# BIRDS-5_1U__X-panel_EM_PUPV_v3_2.net
KiCad netlist of a schematic drawn in EAGLE
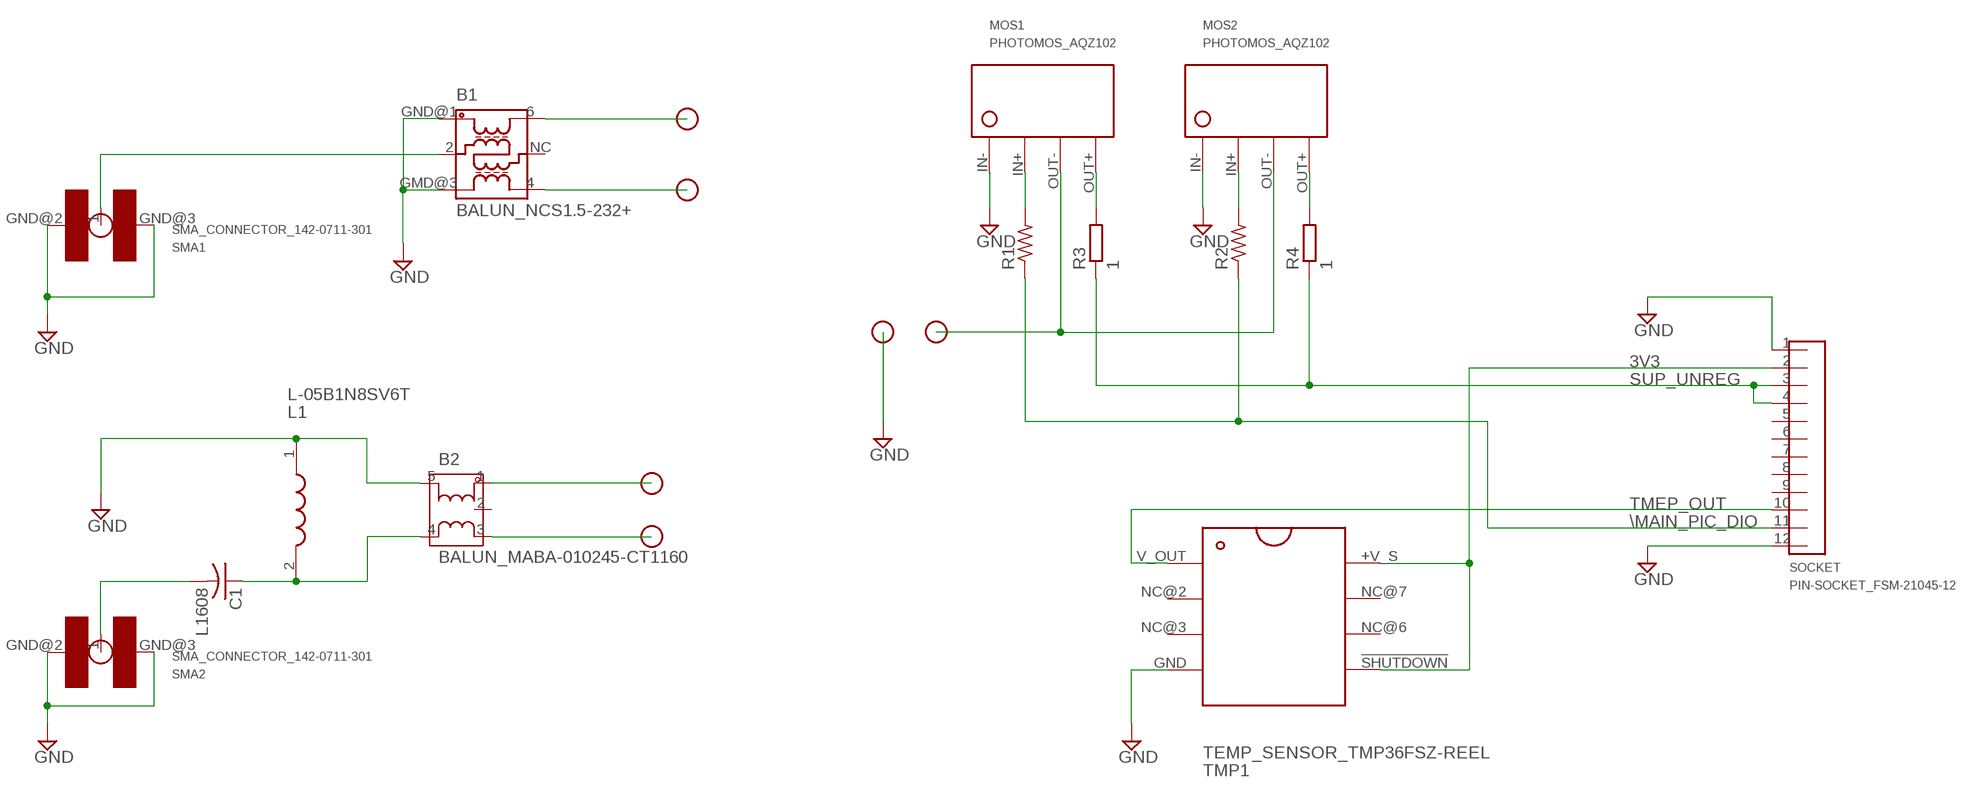
[diagram p0: schematic, sheet 1]

(export (version "E")
  (design (tool "Eeschema 10.0.6"))
  (components
    (comp (ref "B1")
      (value "BALUN_NCS1.5-232+")
      (footprint "eagle-import:NCS1.5-232+")
      (libsource (lib "eagle-import") (part "BALUN_NCS1.5-232+"))
    )
    (comp (ref "B2")
      (value "BALUN_MABA-010245-CT1160")
      (footprint "eagle-import:MABA-010245-CT1160")
      (libsource (lib "eagle-import") (part "BALUN_MABA-010245-CT1160"))
    )
    (comp (ref "C1")
      (value "L1608")
      (footprint "eagle-import:L1608")
      (libsource (lib "eagle-import") (part "L1608"))
    )
    (comp (ref "FD1")
      (value "FEED_POINT_HEAT_KNIFE")
      (footprint "eagle-import:FEED_POINT_HEAT_KNIFE")
      (libsource (lib "eagle-import") (part "FEED_POINT_HEAT_KNIFE"))
    )
    (comp (ref "FD2")
      (value "FEED_POINT_HEAT_KNIFE")
      (footprint "eagle-import:FEED_POINT_HEAT_KNIFE")
      (libsource (lib "eagle-import") (part "FEED_POINT_HEAT_KNIFE"))
    )
    (comp (ref "FP1_UHF")
      (value "FEED_POINT")
      (footprint "eagle-import:FEED_POINT")
      (libsource (lib "eagle-import") (part "FEED_POINT"))
    )
    (comp (ref "FP2_UHF")
      (value "FEED_POINT")
      (footprint "eagle-import:FEED_POINT")
      (libsource (lib "eagle-import") (part "FEED_POINT"))
    )
    (comp (ref "FP3")
      (value "FEED_POINT")
      (footprint "eagle-import:FEED_POINT")
      (libsource (lib "eagle-import") (part "FEED_POINT"))
    )
    (comp (ref "FP4")
      (value "FEED_POINT")
      (footprint "eagle-import:FEED_POINT")
      (libsource (lib "eagle-import") (part "FEED_POINT"))
    )
    (comp (ref "L1")
      (value "L-05B1N8SV6T")
      (footprint "eagle-import:INDC0603X33N")
      (libsource (lib "eagle-import") (part "L-05B1N8SV6T"))
    )
    (comp (ref "MOS1")
      (value "PHOTOMOS_AQZ102")
      (footprint "eagle-import:AQZ102")
      (libsource (lib "eagle-import") (part "PHOTOMOS_AQZ102"))
    )
    (comp (ref "MOS2")
      (value "PHOTOMOS_AQZ102")
      (footprint "eagle-import:AQZ102")
      (libsource (lib "eagle-import") (part "PHOTOMOS_AQZ102"))
    )
    (comp (ref "R1")
      (value "R-US_R0402")
      (footprint "eagle-import:R0402")
      (libsource (lib "eagle-import") (part "R-US_R0402"))
    )
    (comp (ref "R2")
      (value "R-US_R0402")
      (footprint "eagle-import:R0402")
      (libsource (lib "eagle-import") (part "R-US_R0402"))
    )
    (comp (ref "R3")
      (value "1")
      (footprint "eagle-import:R1218")
      (libsource (lib "eagle-import") (part "R-EU_R1218"))
    )
    (comp (ref "R4")
      (value "1")
      (footprint "eagle-import:R1218")
      (libsource (lib "eagle-import") (part "R-EU_R1218"))
    )
    (comp (ref "SMA1")
      (value "SMA_CONNECTOR_142-0711-301")
      (footprint "eagle-import:142-0711-301")
      (libsource (lib "eagle-import") (part "SMA_CONNECTOR_142-0711-301"))
    )
    (comp (ref "SMA2")
      (value "SMA_CONNECTOR_142-0711-301")
      (footprint "eagle-import:142-0711-301")
      (libsource (lib "eagle-import") (part "SMA_CONNECTOR_142-0711-301"))
    )
    (comp (ref "SOCKET")
      (value "PIN-SOCKET_FSM-21045-12")
      (footprint "eagle-import:PIN-SOCKET_FSM-21045-12")
      (libsource (lib "eagle-import") (part "PIN-SOCKET_FSM-21045-12"))
    )
    (comp (ref "TMP1")
      (value "TEMP_SENSOR_TMP36FSZ-REEL")
      (footprint "eagle-import:TMP36FSZ-REEL")
      (libsource (lib "eagle-import") (part "TEMP_SENSOR_TMP36FSZ-REEL"))
    )
  )
  (nets
    (net (code "1") (name "/3V3") (class "Default")
      (node (ref "SOCKET") (pin "2") (pinfunction "P$2_2") (pintype "bidirectional"))
      (node (ref "TMP1") (pin "!SHUTDOWN!") (pinfunction "~{SHUTDOWN}_!SHUTDOWN!") (pintype "input"))
      (node (ref "TMP1") (pin "+V_S") (pinfunction "+V_S_+V_S") (pintype "power_in"))
    )
    (net (code "2") (name "/SUP_UNREG") (class "Default")
      (node (ref "R3") (pin "1") (pinfunction "1_1") (pintype "passive"))
      (node (ref "R4") (pin "1") (pinfunction "1_1") (pintype "passive"))
      (node (ref "SOCKET") (pin "3") (pinfunction "P$3_3") (pintype "bidirectional"))
      (node (ref "SOCKET") (pin "4") (pinfunction "P$4_4") (pintype "bidirectional"))
    )
    (net (code "3") (name "/TMEP_OUT") (class "Default")
      (node (ref "SOCKET") (pin "10") (pinfunction "P$10_10") (pintype "bidirectional"))
      (node (ref "TMP1") (pin "V_OUT") (pinfunction "V_OUT_V_OUT") (pintype "output"))
    )
    (net (code "4") (name "/\\MAIN_PIC_DIO") (class "Default")
      (node (ref "R1") (pin "1") (pinfunction "1_1") (pintype "passive"))
      (node (ref "R2") (pin "1") (pinfunction "1_1") (pintype "passive"))
      (node (ref "SOCKET") (pin "11") (pinfunction "P$11_11") (pintype "bidirectional"))
    )
    (net (code "5") (name "GND") (class "Default")
      (node (ref "B1") (pin "GMD@3") (pinfunction "GND_GMD@3") (pintype "passive"))
      (node (ref "B1") (pin "GND@1") (pinfunction "GND_GND@1") (pintype "passive"))
      (node (ref "B2") (pin "5") (pinfunction "5_5") (pintype "passive"))
      (node (ref "FD2") (pin "FP") (pinfunction "FEED_POINT_FP") (pintype "passive"))
      (node (ref "L1") (pin "1") (pinfunction "1_1") (pintype "bidirectional"))
      (node (ref "MOS1") (pin "IN-") (pinfunction "IN-_IN-") (pintype "bidirectional"))
      (node (ref "MOS2") (pin "IN-") (pinfunction "IN-_IN-") (pintype "bidirectional"))
      (node (ref "SMA1") (pin "GND@2") (pinfunction "GND_GND@2") (pintype "passive"))
      (node (ref "SMA1") (pin "GND@3") (pinfunction "GMD_GND@3") (pintype "passive"))
      (node (ref "SMA2") (pin "GND@2") (pinfunction "GND_GND@2") (pintype "passive"))
      (node (ref "SMA2") (pin "GND@3") (pinfunction "GMD_GND@3") (pintype "passive"))
      (node (ref "SOCKET") (pin "1") (pinfunction "P$1_1") (pintype "bidirectional"))
      (node (ref "SOCKET") (pin "12") (pinfunction "P$12_12") (pintype "bidirectional"))
      (node (ref "TMP1") (pin "GND") (pinfunction "GND_GND") (pintype "power_in"))
    )
    (net (code "6") (name "Net-(B1-Pad2)") (class "Default")
      (node (ref "B1") (pin "2") (pinfunction "2_2") (pintype "passive"))
      (node (ref "SMA1") (pin "1") (pinfunction "1_1") (pintype "passive"))
    )
    (net (code "7") (name "Net-(B2-Pad4)") (class "Default")
      (node (ref "B2") (pin "4") (pinfunction "4_4") (pintype "passive"))
      (node (ref "C1") (pin "1") (pinfunction "1_1") (pintype "passive"))
      (node (ref "L1") (pin "2") (pinfunction "2_2") (pintype "bidirectional"))
    )
    (net (code "8") (name "Net-(C1-Pad2)") (class "Default")
      (node (ref "C1") (pin "2") (pinfunction "2_2") (pintype "passive"))
      (node (ref "SMA2") (pin "1") (pinfunction "1_1") (pintype "passive"))
    )
    (net (code "9") (name "Net-(FD1-FEED_POINT)") (class "Default")
      (node (ref "FD1") (pin "FP") (pinfunction "FEED_POINT_FP") (pintype "passive"))
      (node (ref "MOS1") (pin "OUT-") (pinfunction "OUT-_OUT-") (pintype "bidirectional"))
      (node (ref "MOS2") (pin "OUT-") (pinfunction "OUT-_OUT-") (pintype "bidirectional"))
    )
    (net (code "10") (name "Net-(FP1_UHF-FEED_POINT)") (class "Default")
      (node (ref "B1") (pin "6") (pinfunction "6_6") (pintype "passive"))
      (node (ref "FP1_UHF") (pin "FP") (pinfunction "FEED_POINT_FP") (pintype "passive"))
    )
    (net (code "11") (name "Net-(FP2_UHF-FEED_POINT)") (class "Default")
      (node (ref "B1") (pin "4") (pinfunction "4_4") (pintype "passive"))
      (node (ref "FP2_UHF") (pin "FP") (pinfunction "FEED_POINT_FP") (pintype "passive"))
    )
    (net (code "12") (name "Net-(FP3-FEED_POINT)") (class "Default")
      (node (ref "B2") (pin "1") (pinfunction "1_1") (pintype "passive"))
      (node (ref "FP3") (pin "FP") (pinfunction "FEED_POINT_FP") (pintype "passive"))
    )
    (net (code "13") (name "Net-(FP4-FEED_POINT)") (class "Default")
      (node (ref "B2") (pin "3") (pinfunction "3_3") (pintype "passive"))
      (node (ref "FP4") (pin "FP") (pinfunction "FEED_POINT_FP") (pintype "passive"))
    )
    (net (code "14") (name "Net-(MOS1-PadIN+)") (class "Default")
      (node (ref "MOS1") (pin "IN+") (pinfunction "IN+_IN+") (pintype "bidirectional"))
      (node (ref "R1") (pin "2") (pinfunction "2_2") (pintype "passive"))
    )
    (net (code "15") (name "Net-(MOS1-PadOUT+)") (class "Default")
      (node (ref "MOS1") (pin "OUT+") (pinfunction "OUT+_OUT+") (pintype "bidirectional"))
      (node (ref "R3") (pin "2") (pinfunction "2_2") (pintype "passive"))
    )
    (net (code "16") (name "Net-(MOS2-PadIN+)") (class "Default")
      (node (ref "MOS2") (pin "IN+") (pinfunction "IN+_IN+") (pintype "bidirectional"))
      (node (ref "R2") (pin "2") (pinfunction "2_2") (pintype "passive"))
    )
    (net (code "17") (name "Net-(MOS2-PadOUT+)") (class "Default")
      (node (ref "MOS2") (pin "OUT+") (pinfunction "OUT+_OUT+") (pintype "bidirectional"))
      (node (ref "R4") (pin "2") (pinfunction "2_2") (pintype "passive"))
    )
    (net (code "18") (name "unconnected-(B1-5-PadNC)") (class "Default")
      (node (ref "B1") (pin "NC") (pinfunction "5_NC") (pintype "no_connect"))
    )
    (net (code "19") (name "unconnected-(B2-Pad2)") (class "Default")
      (node (ref "B2") (pin "2") (pinfunction "2_2") (pintype "no_connect"))
    )
    (net (code "20") (name "unconnected-(SOCKET-P$5-Pad5)") (class "Default")
      (node (ref "SOCKET") (pin "5") (pinfunction "P$5_5") (pintype "bidirectional"))
    )
    (net (code "21") (name "unconnected-(SOCKET-P$6-Pad6)") (class "Default")
      (node (ref "SOCKET") (pin "6") (pinfunction "P$6_6") (pintype "bidirectional"))
    )
    (net (code "22") (name "unconnected-(SOCKET-P$7-Pad7)") (class "Default")
      (node (ref "SOCKET") (pin "7") (pinfunction "P$7_7") (pintype "bidirectional"))
    )
    (net (code "23") (name "unconnected-(SOCKET-P$8-Pad8)") (class "Default")
      (node (ref "SOCKET") (pin "8") (pinfunction "P$8_8") (pintype "bidirectional"))
    )
    (net (code "24") (name "unconnected-(SOCKET-P$9-Pad9)") (class "Default")
      (node (ref "SOCKET") (pin "9") (pinfunction "P$9_9") (pintype "bidirectional"))
    )
    (net (code "25") (name "unconnected-(TMP1-NC-PadNC@2)") (class "Default")
      (node (ref "TMP1") (pin "NC@2") (pinfunction "NC_NC@2") (pintype "no_connect"))
    )
    (net (code "26") (name "unconnected-(TMP1-NC-PadNC@3)") (class "Default")
      (node (ref "TMP1") (pin "NC@3") (pinfunction "NC_NC@3") (pintype "no_connect"))
    )
    (net (code "27") (name "unconnected-(TMP1-NC-PadNC@6)") (class "Default")
      (node (ref "TMP1") (pin "NC@6") (pinfunction "NC_NC@6") (pintype "no_connect"))
    )
    (net (code "28") (name "unconnected-(TMP1-NC-PadNC@7)") (class "Default")
      (node (ref "TMP1") (pin "NC@7") (pinfunction "NC_NC@7") (pintype "no_connect"))
    )
  )
)
